# 05_LMS7002M_RF1.net
KiCad netlist of a schematic drawn in Altium Designer
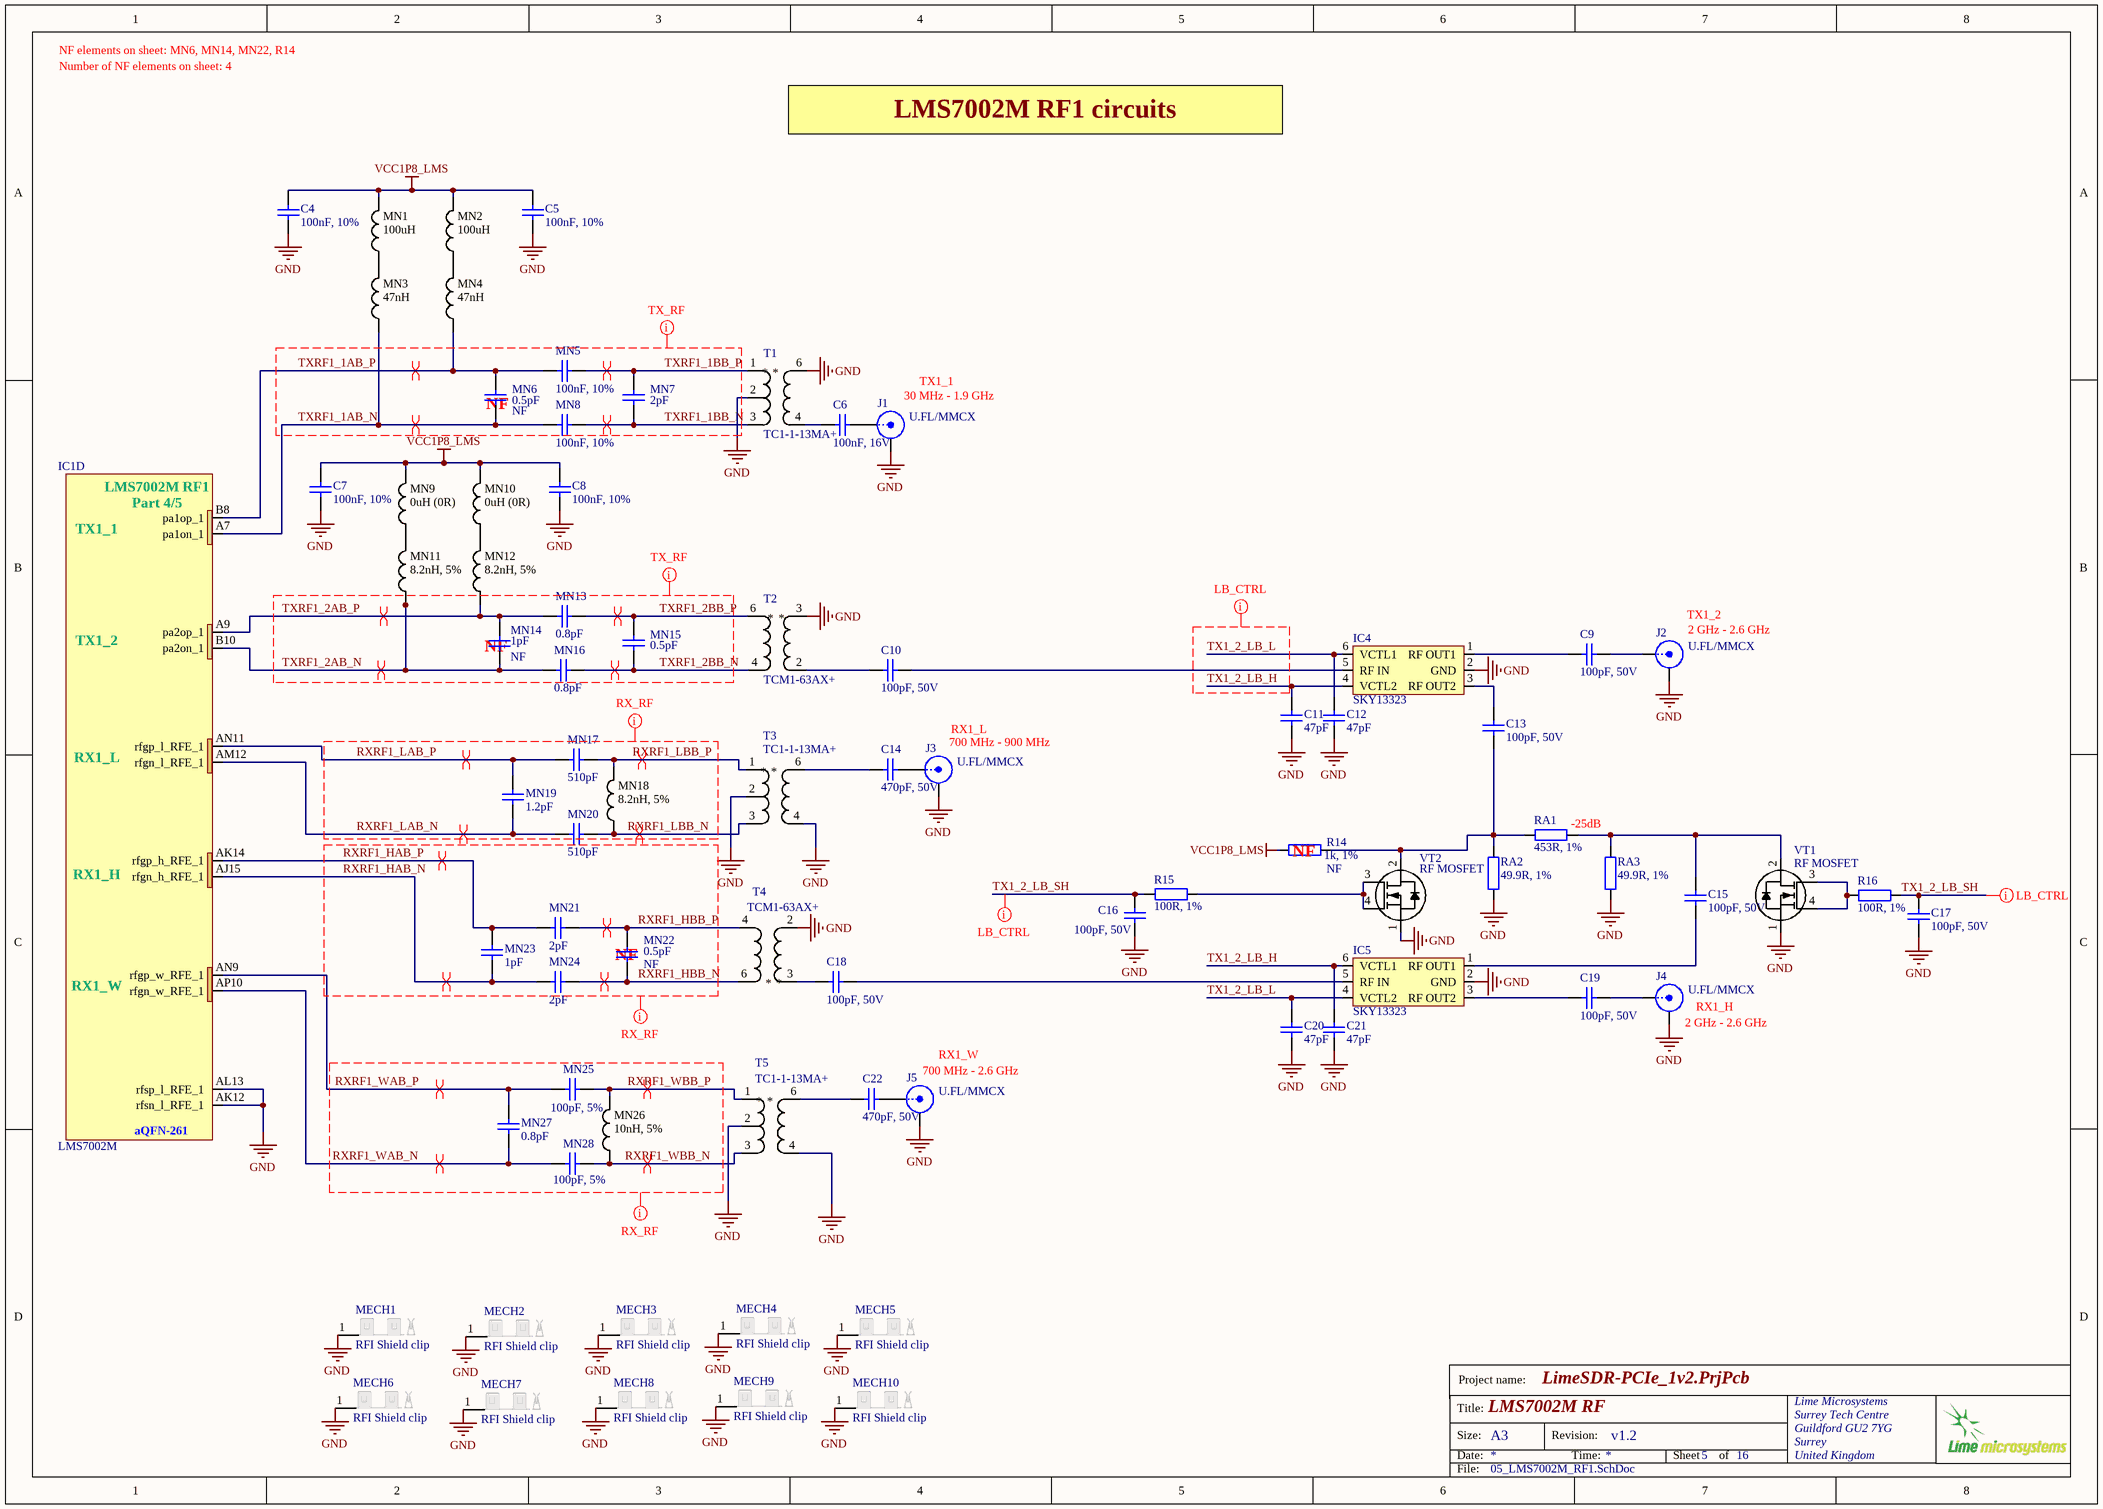
[diagram p0: 05_LMS7002M_RF1.SchDoc]

(export (version "E")
  (design (tool "Eeschema 10.0.6"))
  (components
    (comp (ref "C4")
      (value "100nF, 10%")
      (footprint "CAP0402")
      (fields
        (field (name "MANUFACTURER") "Murata Electronics")
        (field (name "TOLERANCE") "10 %")
        (field (name "MANUFACTURER PART NUMBER") "GRM155R71C104KA88D")
      )
      (libsource (lib "LimeMicroAltiumLib_schLib") (part "Cap_0402"))
    )
    (comp (ref "C5")
      (value "100nF, 10%")
      (footprint "CAP0402")
      (fields
        (field (name "MANUFACTURER") "Murata Electronics")
        (field (name "TOLERANCE") "10 %")
        (field (name "MANUFACTURER PART NUMBER") "GRM155R71C104KA88D")
      )
      (libsource (lib "LimeMicroAltiumLib_schLib") (part "Cap_0402"))
    )
    (comp (ref "C6")
      (value "100nF, 16V")
      (footprint "CAP0402")
      (fields
        (field (name "MANUFACTURER") "Murata Electronics")
        (field (name "TOLERANCE") "10 %")
        (field (name "MANUFACTURER PART NUMBER") "GRM155R71C104KA88D")
      )
      (libsource (lib "LimeMicroAltiumLib_schLib") (part "Cap_0402"))
    )
    (comp (ref "C7")
      (value "100nF, 10%")
      (footprint "CAP0402")
      (fields
        (field (name "MANUFACTURER") "Murata Electronics")
        (field (name "TOLERANCE") "10 %")
        (field (name "MANUFACTURER PART NUMBER") "GRM155R71C104KA88D")
      )
      (libsource (lib "LimeMicroAltiumLib_schLib") (part "Cap_0402"))
    )
    (comp (ref "C8")
      (value "100nF, 10%")
      (footprint "CAP0402")
      (fields
        (field (name "MANUFACTURER") "Murata Electronics")
        (field (name "TOLERANCE") "10 %")
        (field (name "MANUFACTURER PART NUMBER") "GRM155R71C104KA88D")
      )
      (libsource (lib "LimeMicroAltiumLib_schLib") (part "Cap_0402"))
    )
    (comp (ref "C9")
      (value "100pF, 50V")
      (footprint "CAP0402")
      (fields (field (name "TOLERANCE") "±5%") (field (name "MANUFACTURER") "Yageo"))
      (libsource (lib "LimeMicroAltiumLib_schLib") (part "Cap_0402"))
    )
    (comp (ref "C10")
      (value "100pF, 50V")
      (footprint "CAP0402")
      (fields (field (name "TOLERANCE") "±5%") (field (name "MANUFACTURER") "Yageo"))
      (libsource (lib "LimeMicroAltiumLib_schLib") (part "Cap_0402"))
    )
    (comp (ref "C11")
      (value "47pF")
      (footprint "CAP0402")
      (fields (field (name "TOLERANCE") "±1%") (field (name "MANUFACTURER") "TDK Corporation"))
      (libsource (lib "LimeMicroAltiumLib_schLib") (part "Cap_0402"))
    )
    (comp (ref "C12")
      (value "47pF")
      (footprint "CAP0402")
      (fields (field (name "TOLERANCE") "±1%") (field (name "MANUFACTURER") "TDK Corporation"))
      (libsource (lib "LimeMicroAltiumLib_schLib") (part "Cap_0402"))
    )
    (comp (ref "C13")
      (value "100pF, 50V")
      (footprint "CAP0402")
      (fields (field (name "TOLERANCE") "±5%") (field (name "MANUFACTURER") "Yageo"))
      (libsource (lib "LimeMicroAltiumLib_schLib") (part "Cap_0402"))
    )
    (comp (ref "C14")
      (value "470pF, 50V")
      (footprint "CAP0402")
      (fields
        (field (name "MANUFACTURER PART NUMBER") "C1005C0G1H471J050BA")
        (field (name "TOLERANCE") "±5%")
        (field (name "MANUFACTURER") "TDK Corporation")
      )
      (libsource (lib "LimeMicroAltiumLib_schLib") (part "Cap_0402"))
    )
    (comp (ref "C15")
      (value "100pF, 50V")
      (footprint "CAP0402")
      (fields (field (name "TOLERANCE") "±5%") (field (name "MANUFACTURER") "Yageo"))
      (libsource (lib "LimeMicroAltiumLib_schLib") (part "Cap_0402"))
    )
    (comp (ref "C16")
      (value "100pF, 50V")
      (footprint "CAP0402")
      (fields (field (name "TOLERANCE") "±5%") (field (name "MANUFACTURER") "Yageo"))
      (libsource (lib "LimeMicroAltiumLib_schLib") (part "Cap_0402"))
    )
    (comp (ref "C17")
      (value "100pF, 50V")
      (footprint "CAP0402")
      (fields (field (name "TOLERANCE") "±5%") (field (name "MANUFACTURER") "Yageo"))
      (libsource (lib "LimeMicroAltiumLib_schLib") (part "Cap_0402"))
    )
    (comp (ref "C18")
      (value "100pF, 50V")
      (footprint "CAP0402")
      (fields (field (name "TOLERANCE") "±5%") (field (name "MANUFACTURER") "Yageo"))
      (libsource (lib "LimeMicroAltiumLib_schLib") (part "Cap_0402"))
    )
    (comp (ref "C19")
      (value "100pF, 50V")
      (footprint "CAP0402")
      (fields (field (name "TOLERANCE") "±5%") (field (name "MANUFACTURER") "Yageo"))
      (libsource (lib "LimeMicroAltiumLib_schLib") (part "Cap_0402"))
    )
    (comp (ref "C20")
      (value "47pF")
      (footprint "CAP0402")
      (fields (field (name "TOLERANCE") "±1%") (field (name "MANUFACTURER") "TDK Corporation"))
      (libsource (lib "LimeMicroAltiumLib_schLib") (part "Cap_0402"))
    )
    (comp (ref "C21")
      (value "47pF")
      (footprint "CAP0402")
      (fields (field (name "TOLERANCE") "±1%") (field (name "MANUFACTURER") "TDK Corporation"))
      (libsource (lib "LimeMicroAltiumLib_schLib") (part "Cap_0402"))
    )
    (comp (ref "C22")
      (value "470pF, 50V")
      (footprint "CAP0402")
      (fields
        (field (name "MANUFACTURER PART NUMBER") "C1005C0G1H471J050BA")
        (field (name "TOLERANCE") "±5%")
        (field (name "MANUFACTURER") "TDK Corporation")
      )
      (libsource (lib "LimeMicroAltiumLib_schLib") (part "Cap_0402"))
    )
    (comp (ref "IC1")
      (value "LMS7002M")
      (footprint "LMS7002M_v2")
      (fields (field (name "MANUFACTURER") "Lime Microsystems"))
      (libsource (lib "LimeMicroAltiumLib_schLib") (part "LMS7002M"))
    )
    (comp (ref "IC4")
      (value "SKY13323")
      (footprint "SKY13323-378LF")
      (description "SKY13323-378LF: 0.1-3.0 GHz GaAs SPDT Switch")
      (fields (field (name "MANUFACTURER") "Skyworks Solutions Inc."))
      (libsource (lib "LimeMicroAltiumLib_schLib") (part "SKY13323"))
    )
    (comp (ref "IC5")
      (value "SKY13323")
      (footprint "SKY13323-378LF")
      (description "SKY13323-378LF: 0.1-3.0 GHz GaAs SPDT Switch")
      (fields (field (name "MANUFACTURER") "Skyworks Solutions Inc."))
      (libsource (lib "LimeMicroAltiumLib_schLib") (part "SKY13323"))
    )
    (comp (ref "J1")
      (value "U.FL/MMCX")
      (footprint "MMCX_UFL_conn_u")
      (description "CONN UMC RCPT STR 50 OHM SMD")
      (fields (field (name "MANUFACTURER") "Molex, LLC"))
      (libsource (lib "LimeMicroAltiumLib_schLib") (part "RF_IF_connector"))
    )
    (comp (ref "J2")
      (value "U.FL/MMCX")
      (footprint "MMCX_UFL_conn_u")
      (description "CONN UMC RCPT STR 50 OHM SMD")
      (fields (field (name "MANUFACTURER") "Molex, LLC"))
      (libsource (lib "LimeMicroAltiumLib_schLib") (part "RF_IF_connector"))
    )
    (comp (ref "J3")
      (value "U.FL/MMCX")
      (footprint "MMCX_UFL_conn_u")
      (description "CONN UMC RCPT STR 50 OHM SMD")
      (fields (field (name "MANUFACTURER") "Molex, LLC"))
      (libsource (lib "LimeMicroAltiumLib_schLib") (part "RF_IF_connector"))
    )
    (comp (ref "J4")
      (value "U.FL/MMCX")
      (footprint "MMCX_UFL_conn_u")
      (description "CONN UMC RCPT STR 50 OHM SMD")
      (fields (field (name "MANUFACTURER") "Molex, LLC"))
      (libsource (lib "LimeMicroAltiumLib_schLib") (part "RF_IF_connector"))
    )
    (comp (ref "J5")
      (value "U.FL/MMCX")
      (footprint "MMCX_UFL_conn_u")
      (description "CONN UMC RCPT STR 50 OHM SMD")
      (fields (field (name "MANUFACTURER") "Molex, LLC"))
      (libsource (lib "LimeMicroAltiumLib_schLib") (part "RF_IF_connector"))
    )
    (comp (ref "MECH1")
      (value "RFI Shield clip")
      (footprint "RFI_SHIELD_CLPS_MINI")
      (fields (field (name "MANUFACTURER") "HARWIN"))
      (libsource (lib "LimeMicroAltiumLib_schLib") (part "RFI_SHIELD_CLIP"))
    )
    (comp (ref "MECH2")
      (value "RFI Shield clip")
      (footprint "RFI_SHIELD_CLPS_MINI")
      (fields (field (name "MANUFACTURER") "HARWIN"))
      (libsource (lib "LimeMicroAltiumLib_schLib") (part "RFI_SHIELD_CLIP"))
    )
    (comp (ref "MECH3")
      (value "RFI Shield clip")
      (footprint "RFI_SHIELD_CLPS_MINI")
      (fields (field (name "MANUFACTURER") "HARWIN"))
      (libsource (lib "LimeMicroAltiumLib_schLib") (part "RFI_SHIELD_CLIP"))
    )
    (comp (ref "MECH4")
      (value "RFI Shield clip")
      (footprint "RFI_SHIELD_CLPS_MINI")
      (fields (field (name "MANUFACTURER") "HARWIN"))
      (libsource (lib "LimeMicroAltiumLib_schLib") (part "RFI_SHIELD_CLIP"))
    )
    (comp (ref "MECH5")
      (value "RFI Shield clip")
      (footprint "RFI_SHIELD_CLPS_MINI")
      (fields (field (name "MANUFACTURER") "HARWIN"))
      (libsource (lib "LimeMicroAltiumLib_schLib") (part "RFI_SHIELD_CLIP"))
    )
    (comp (ref "MECH6")
      (value "RFI Shield clip")
      (footprint "RFI_SHIELD_CLPS_MINI")
      (fields (field (name "MANUFACTURER") "HARWIN"))
      (libsource (lib "LimeMicroAltiumLib_schLib") (part "RFI_SHIELD_CLIP"))
    )
    (comp (ref "MECH7")
      (value "RFI Shield clip")
      (footprint "RFI_SHIELD_CLPS_MINI")
      (fields (field (name "MANUFACTURER") "HARWIN"))
      (libsource (lib "LimeMicroAltiumLib_schLib") (part "RFI_SHIELD_CLIP"))
    )
    (comp (ref "MECH8")
      (value "RFI Shield clip")
      (footprint "RFI_SHIELD_CLPS_MINI")
      (fields (field (name "MANUFACTURER") "HARWIN"))
      (libsource (lib "LimeMicroAltiumLib_schLib") (part "RFI_SHIELD_CLIP"))
    )
    (comp (ref "MECH9")
      (value "RFI Shield clip")
      (footprint "RFI_SHIELD_CLPS_MINI")
      (fields (field (name "MANUFACTURER") "HARWIN"))
      (libsource (lib "LimeMicroAltiumLib_schLib") (part "RFI_SHIELD_CLIP"))
    )
    (comp (ref "MECH10")
      (value "RFI Shield clip")
      (footprint "RFI_SHIELD_CLPS_MINI")
      (fields (field (name "MANUFACTURER") "HARWIN"))
      (libsource (lib "LimeMicroAltiumLib_schLib") (part "RFI_SHIELD_CLIP"))
    )
    (comp (ref "MN1")
      (value "100uH")
      (footprint "RES0805")
      (fields
        (field (name "TOLERANCE") "±10%")
        (field (name "MANUFACTURER") "TDK Corporation")
        (field (name "MANUFACTURER PART NUMBER") "MLF2012C101KT000")
      )
      (libsource (lib "LimeMicroAltiumLib_schLib") (part "Inductor_0603"))
    )
    (comp (ref "MN2")
      (value "100uH")
      (footprint "RES0805")
      (fields
        (field (name "TOLERANCE") "±10%")
        (field (name "MANUFACTURER") "TDK Corporation")
        (field (name "MANUFACTURER PART NUMBER") "MLF2012C101KT000")
      )
      (libsource (lib "LimeMicroAltiumLib_schLib") (part "Inductor_0603"))
    )
    (comp (ref "MN3")
      (value "47nH")
      (footprint "RES0402")
      (fields
        (field (name "MANUFACTURER") "COILCRAFT")
        (field (name "MANUFACTURER PART NUMBER") "0402HP-47NXJLU")
      )
      (libsource (lib "LimeMicroAltiumLib_schLib") (part "Inductor_0603"))
    )
    (comp (ref "MN4")
      (value "47nH")
      (footprint "RES0402")
      (fields
        (field (name "MANUFACTURER") "COILCRAFT")
        (field (name "MANUFACTURER PART NUMBER") "0402HP-47NXJLU")
      )
      (libsource (lib "LimeMicroAltiumLib_schLib") (part "Inductor_0603"))
    )
    (comp (ref "MN5")
      (value "100nF, 10%")
      (footprint "CAP0402")
      (fields
        (field (name "MANUFACTURER") "Murata Electronics")
        (field (name "TOLERANCE") "10 %")
        (field (name "MANUFACTURER PART NUMBER") "GRM155R71C104KA88D")
      )
      (libsource (lib "LimeMicroAltiumLib_schLib") (part "Cap_0402"))
    )
    (comp (ref "MN6")
      (value "0.5pF")
      (footprint "CAP0402")
      (fields
        (field (name "ASSEMBLY INFO") "NF")
        (field (name "TOLERANCE") "±0.25pF")
        (field (name "MANUFACTURER") "Yageo")
      )
      (libsource (lib "LimeMicroAltiumLib_schLib") (part "Cap_0402"))
    )
    (comp (ref "MN7")
      (value "2pF")
      (footprint "CAP0402")
      (fields (field (name "MANUFACTURER PART NUMBER") "04025U2R0BAT2A") (field (name "MANUFACTURER") "AVX"))
      (libsource (lib "LimeMicroAltiumLib_schLib") (part "Cap_0402"))
    )
    (comp (ref "MN8")
      (value "100nF, 10%")
      (footprint "CAP0402")
      (fields
        (field (name "MANUFACTURER") "Murata Electronics")
        (field (name "TOLERANCE") "10 %")
        (field (name "MANUFACTURER PART NUMBER") "GRM155R71C104KA88D")
      )
      (libsource (lib "LimeMicroAltiumLib_schLib") (part "Cap_0402"))
    )
    (comp (ref "MN9")
      (value "0uH (0R)")
      (footprint "RES0805")
      (fields
        (field (name "MANUFACTURER") "BOURNS")
        (field (name "MANUFACTURER PART NUMBER") "CR0805-J/-000ELF")
      )
      (libsource (lib "LimeMicroAltiumLib_schLib") (part "Inductor_0603"))
    )
    (comp (ref "MN10")
      (value "0uH (0R)")
      (footprint "RES0805")
      (fields
        (field (name "MANUFACTURER") "BOURNS")
        (field (name "MANUFACTURER PART NUMBER") "CR0805-J/-000ELF")
      )
      (libsource (lib "LimeMicroAltiumLib_schLib") (part "Inductor_0603"))
    )
    (comp (ref "MN11")
      (value "8.2nH, 5%")
      (footprint "RES0402")
      (fields (field (name "MANUFACTURER") "COILCRAFT"))
      (libsource (lib "LimeMicroAltiumLib_schLib") (part "Inductor_0603"))
    )
    (comp (ref "MN12")
      (value "8.2nH, 5%")
      (footprint "RES0402")
      (fields (field (name "MANUFACTURER") "COILCRAFT"))
      (libsource (lib "LimeMicroAltiumLib_schLib") (part "Inductor_0603"))
    )
    (comp (ref "MN13")
      (value "0.8pF")
      (footprint "CAP0402")
      (fields
        (field (name "TOLERANCE") "±0.1pF")
        (field (name "MANUFACTURER") "Murata Electronics North America")
        (field (name "MANUFACTURER PART NUMBER") "GRM1555C1HR80BA01D")
      )
      (libsource (lib "LimeMicroAltiumLib_schLib") (part "Cap_0402"))
    )
    (comp (ref "MN14")
      (value "1pF")
      (footprint "CAP0402")
      (fields
        (field (name "ASSEMBLY INFO") "NF")
        (field (name "MANUFACTURER") "TDK Corporation")
        (field (name "TOLERANCE") "±0.1pF")
      )
      (libsource (lib "LimeMicroAltiumLib_schLib") (part "Cap_0402"))
    )
    (comp (ref "MN15")
      (value "0.5pF")
      (footprint "CAP0402")
      (fields (field (name "TOLERANCE") "±0.25pF") (field (name "MANUFACTURER") "Yageo"))
      (libsource (lib "LimeMicroAltiumLib_schLib") (part "Cap_0402"))
    )
    (comp (ref "MN16")
      (value "0.8pF")
      (footprint "CAP0402")
      (fields
        (field (name "TOLERANCE") "±0.1pF")
        (field (name "MANUFACTURER") "Murata Electronics North America")
        (field (name "MANUFACTURER PART NUMBER") "GRM1555C1HR80BA01D")
      )
      (libsource (lib "LimeMicroAltiumLib_schLib") (part "Cap_0402"))
    )
    (comp (ref "MN17")
      (value "510pF")
      (footprint "CAP0402")
      (fields
        (field (name "TOLERANCE") "±5%")
        (field (name "MANUFACTURER") "Murata Electronics North America")
        (field (name "MANUFACTURER PART NUMBER") "GRM1555C1H511JA01D")
      )
      (libsource (lib "LimeMicroAltiumLib_schLib") (part "Cap_0402"))
    )
    (comp (ref "MN18")
      (value "8.2nH, 5%")
      (footprint "RES0402")
      (fields (field (name "MANUFACTURER") "COILCRAFT"))
      (libsource (lib "LimeMicroAltiumLib_schLib") (part "Inductor_0603"))
    )
    (comp (ref "MN19")
      (value "1.2pF")
      (footprint "CAP0402")
      (fields
        (field (name "MANUFACTURER") "Murata Electronics North America")
        (field (name "MANUFACTURER PART NUMBER") "GRM1555C1H1R2CA01D")
        (field (name "TOLERANCE") "±0.25pF")
      )
      (libsource (lib "LimeMicroAltiumLib_schLib") (part "Cap_0402"))
    )
    (comp (ref "MN20")
      (value "510pF")
      (footprint "CAP0402")
      (fields
        (field (name "TOLERANCE") "±5%")
        (field (name "MANUFACTURER") "Murata Electronics North America")
        (field (name "MANUFACTURER PART NUMBER") "GRM1555C1H511JA01D")
      )
      (libsource (lib "LimeMicroAltiumLib_schLib") (part "Cap_0402"))
    )
    (comp (ref "MN21")
      (value "2pF")
      (footprint "CAP0402")
      (fields (field (name "MANUFACTURER PART NUMBER") "04025U2R0BAT2A") (field (name "MANUFACTURER") "AVX"))
      (libsource (lib "LimeMicroAltiumLib_schLib") (part "Cap_0402"))
    )
    (comp (ref "MN22")
      (value "0.5pF")
      (footprint "CAP0402")
      (fields
        (field (name "ASSEMBLY INFO") "NF")
        (field (name "TOLERANCE") "±0.25pF")
        (field (name "MANUFACTURER") "Yageo")
      )
      (libsource (lib "LimeMicroAltiumLib_schLib") (part "Cap_0402"))
    )
    (comp (ref "MN23")
      (value "1pF")
      (footprint "CAP0402")
      (fields (field (name "MANUFACTURER") "TDK Corporation") (field (name "TOLERANCE") "±0.1pF"))
      (libsource (lib "LimeMicroAltiumLib_schLib") (part "Cap_0402"))
    )
    (comp (ref "MN24")
      (value "2pF")
      (footprint "CAP0402")
      (fields (field (name "MANUFACTURER PART NUMBER") "04025U2R0BAT2A") (field (name "MANUFACTURER") "AVX"))
      (libsource (lib "LimeMicroAltiumLib_schLib") (part "Cap_0402"))
    )
    (comp (ref "MN25")
      (value "100pF, 5%")
      (footprint "CAP0402")
      (fields (field (name "TOLERANCE") "±5%") (field (name "MANUFACTURER") "Yageo"))
      (libsource (lib "LimeMicroAltiumLib_schLib") (part "Cap_0402"))
    )
    (comp (ref "MN26")
      (value "10nH, 5%")
      (footprint "RES0402")
      (fields (field (name "MANUFACTURER") "COILCRAFT"))
      (libsource (lib "LimeMicroAltiumLib_schLib") (part "Inductor_0603"))
    )
    (comp (ref "MN27")
      (value "0.8pF")
      (footprint "CAP0402")
      (fields
        (field (name "TOLERANCE") "±0.1pF")
        (field (name "MANUFACTURER") "Murata Electronics North America")
        (field (name "MANUFACTURER PART NUMBER") "GRM1555C1HR80BA01D")
      )
      (libsource (lib "LimeMicroAltiumLib_schLib") (part "Cap_0402"))
    )
    (comp (ref "MN28")
      (value "100pF, 5%")
      (footprint "CAP0402")
      (fields (field (name "TOLERANCE") "±5%") (field (name "MANUFACTURER") "Yageo"))
      (libsource (lib "LimeMicroAltiumLib_schLib") (part "Cap_0402"))
    )
    (comp (ref "R14")
      (value "1k, 1%")
      (footprint "RES0402")
      (fields
        (field (name "ASSEMBLY INFO") "NF")
        (field (name "MANUFACTURER") "Stackpole Electronics Inc")
        (field (name "TOLERANCE") "±1%")
      )
      (libsource (lib "LimeMicroAltiumLib_schLib") (part "Res_0402"))
    )
    (comp (ref "R15")
      (value "100R, 1%")
      (footprint "RES0402")
      (fields (field (name "TOLERANCE") "±1%") (field (name "MANUFACTURER") "Stackpole Electronics Inc."))
      (libsource (lib "LimeFPGAboard_schLib") (part "Res_0402"))
    )
    (comp (ref "R16")
      (value "100R, 1%")
      (footprint "RES0402")
      (fields (field (name "TOLERANCE") "±1%") (field (name "MANUFACTURER") "Stackpole Electronics Inc."))
      (libsource (lib "LimeFPGAboard_schLib") (part "Res_0402"))
    )
    (comp (ref "RA1")
      (value "453R, 1%")
      (footprint "RES0402")
      (fields (field (name "MANUFACTURER") "Yageo") (field (name "TOLERANCE") "±1%"))
      (libsource (lib "LimeMicroAltiumLib_schLib") (part "Res_0402"))
    )
    (comp (ref "RA2")
      (value "49.9R, 1%")
      (footprint "RES0402")
      (fields
        (field (name "TOLERANCE") "±1%")
        (field (name "MANUFACTURER") "Samsung Electro-Mechanics America, Inc.")
        (field (name "MANUFACTURER PART NUMBER") "RC1005F49R9CS")
      )
      (libsource (lib "LimeMicroAltiumLib_schLib") (part "Res_0402"))
    )
    (comp (ref "RA3")
      (value "49.9R, 1%")
      (footprint "RES0402")
      (fields
        (field (name "TOLERANCE") "±1%")
        (field (name "MANUFACTURER") "Samsung Electro-Mechanics America, Inc.")
        (field (name "MANUFACTURER PART NUMBER") "RC1005F49R9CS")
      )
      (libsource (lib "LimeMicroAltiumLib_schLib") (part "Res_0402"))
    )
    (comp (ref "T1")
      (value "TC1-1-13MA+")
      (footprint "TC1-1-13MA+_v2")
      (fields (field (name "MANUFACTURER") "Mini-Circuits"))
      (libsource (lib "LimeMicroAltiumLib_schLib") (part "Balun"))
    )
    (comp (ref "T2")
      (value "TCM1-63AX+")
      (footprint "TCM1-63AX+_v2")
      (fields (field (name "MANUFACTURER") "Mini-circuits"))
      (libsource (lib "LimeMicroAltiumLib_schLib") (part "Balun_v2"))
    )
    (comp (ref "T3")
      (value "TC1-1-13MA+")
      (footprint "TC1-1-13MA+_v2")
      (fields (field (name "MANUFACTURER") "Mini-Circuits"))
      (libsource (lib "LimeMicroAltiumLib_schLib") (part "Balun"))
    )
    (comp (ref "T4")
      (value "TCM1-63AX+")
      (footprint "TCM1-63AX+_v2")
      (fields (field (name "MANUFACTURER") "Mini-circuits"))
      (libsource (lib "") (part "Balun_v2_1"))
    )
    (comp (ref "T5")
      (value "TC1-1-13MA+")
      (footprint "TC1-1-13MA+_v2")
      (fields (field (name "MANUFACTURER") "Mini-Circuits"))
      (libsource (lib "LimeMicroAltiumLib_schLib") (part "Balun"))
    )
    (comp (ref "VT1")
      (value "RF MOSFET")
      (footprint "BF1105R_SOT143R4")
      (fields (field (name "MANUFACTURER") "NXP Semiconductors"))
      (libsource (lib "LimeMicroAltiumLib_schLib") (part "BF1105R,215"))
    )
    (comp (ref "VT2")
      (value "RF MOSFET")
      (footprint "BF1105R_SOT143R4")
      (fields (field (name "MANUFACTURER") "NXP Semiconductors"))
      (libsource (lib "LimeMicroAltiumLib_schLib") (part "BF1105R,215"))
    )
  )
  (nets
    (net (code "1") (name "/RXRF1_HAB_N") (class "Default")
      (node (ref "IC1") (pin "AJ15") (pinfunction "rfgn_h_RFE_1_AJ15") (pintype "passive"))
      (node (ref "MN23") (pin "1") (pinfunction "1_1") (pintype "passive"))
      (node (ref "MN24") (pin "2") (pinfunction "2_2") (pintype "passive"))
    )
    (net (code "2") (name "/RXRF1_HAB_P") (class "Default")
      (node (ref "IC1") (pin "AK14") (pinfunction "rfgp_h_RFE_1_AK14") (pintype "passive"))
      (node (ref "MN21") (pin "2") (pinfunction "2_2") (pintype "passive"))
      (node (ref "MN23") (pin "2") (pinfunction "2_2") (pintype "passive"))
    )
    (net (code "3") (name "/RXRF1_HBB_N") (class "Default")
      (node (ref "MN22") (pin "1") (pinfunction "1_1") (pintype "passive"))
      (node (ref "MN24") (pin "1") (pinfunction "1_1") (pintype "passive"))
      (node (ref "T4") (pin "6") (pinfunction "6_6") (pintype "passive"))
    )
    (net (code "4") (name "/RXRF1_HBB_P") (class "Default")
      (node (ref "MN21") (pin "1") (pinfunction "1_1") (pintype "passive"))
      (node (ref "MN22") (pin "2") (pinfunction "2_2") (pintype "passive"))
      (node (ref "T4") (pin "4") (pinfunction "4_4") (pintype "passive"))
    )
    (net (code "5") (name "/RXRF1_LAB_N") (class "Default")
      (node (ref "IC1") (pin "AM12") (pinfunction "rfgn_l_RFE_1_AM12") (pintype "passive"))
      (node (ref "MN19") (pin "1") (pinfunction "1_1") (pintype "passive"))
      (node (ref "MN20") (pin "2") (pinfunction "2_2") (pintype "passive"))
    )
    (net (code "6") (name "/RXRF1_LAB_P") (class "Default")
      (node (ref "IC1") (pin "AN11") (pinfunction "rfgp_l_RFE_1_AN11") (pintype "passive"))
      (node (ref "MN17") (pin "2") (pinfunction "2_2") (pintype "passive"))
      (node (ref "MN19") (pin "2") (pinfunction "2_2") (pintype "passive"))
    )
    (net (code "7") (name "/RXRF1_LBB_N") (class "Default")
      (node (ref "MN18") (pin "1") (pinfunction "1_1") (pintype "passive"))
      (node (ref "MN20") (pin "1") (pinfunction "1_1") (pintype "passive"))
      (node (ref "T3") (pin "3") (pinfunction "3_3") (pintype "passive"))
    )
    (net (code "8") (name "/RXRF1_LBB_P") (class "Default")
      (node (ref "MN17") (pin "1") (pinfunction "1_1") (pintype "passive"))
      (node (ref "MN18") (pin "2") (pinfunction "2_2") (pintype "passive"))
      (node (ref "T3") (pin "1") (pinfunction "1_1") (pintype "passive"))
    )
    (net (code "9") (name "/RXRF1_WAB_N") (class "Default")
      (node (ref "IC1") (pin "AP10") (pinfunction "rfgn_w_RFE_1_AP10") (pintype "passive"))
      (node (ref "MN27") (pin "2") (pinfunction "2_2") (pintype "passive"))
      (node (ref "MN28") (pin "2") (pinfunction "2_2") (pintype "passive"))
    )
    (net (code "10") (name "/RXRF1_WAB_P") (class "Default")
      (node (ref "IC1") (pin "AN9") (pinfunction "rfgp_w_RFE_1_AN9") (pintype "passive"))
      (node (ref "MN25") (pin "2") (pinfunction "2_2") (pintype "passive"))
      (node (ref "MN27") (pin "1") (pinfunction "1_1") (pintype "passive"))
    )
    (net (code "11") (name "/RXRF1_WBB_N") (class "Default")
      (node (ref "MN26") (pin "1") (pinfunction "1_1") (pintype "passive"))
      (node (ref "MN28") (pin "1") (pinfunction "1_1") (pintype "passive"))
      (node (ref "T5") (pin "3") (pinfunction "3_3") (pintype "passive"))
    )
    (net (code "12") (name "/RXRF1_WBB_P") (class "Default")
      (node (ref "MN25") (pin "1") (pinfunction "1_1") (pintype "passive"))
      (node (ref "MN26") (pin "2") (pinfunction "2_2") (pintype "passive"))
      (node (ref "T5") (pin "1") (pinfunction "1_1") (pintype "passive"))
    )
    (net (code "13") (name "/TX1_2_LB_H") (class "Default")
      (node (ref "C11") (pin "2") (pinfunction "2_2") (pintype "passive"))
      (node (ref "C21") (pin "2") (pinfunction "2_2") (pintype "passive"))
      (node (ref "IC4") (pin "4") (pinfunction "VCTL2_4") (pintype "input"))
      (node (ref "IC5") (pin "6") (pinfunction "VCTL1_6") (pintype "input"))
    )
    (net (code "14") (name "/TX1_2_LB_L") (class "Default")
      (node (ref "C12") (pin "2") (pinfunction "2_2") (pintype "passive"))
      (node (ref "C20") (pin "2") (pinfunction "2_2") (pintype "passive"))
      (node (ref "IC4") (pin "6") (pinfunction "VCTL1_6") (pintype "input"))
      (node (ref "IC5") (pin "4") (pinfunction "VCTL2_4") (pintype "input"))
    )
    (net (code "15") (name "/TX1_2_LB_SH") (class "Default")
      (node (ref "C16") (pin "1") (pinfunction "1_1") (pintype "passive"))
      (node (ref "C17") (pin "1") (pinfunction "1_1") (pintype "passive"))
      (node (ref "R15") (pin "2") (pinfunction "2_2") (pintype "passive"))
      (node (ref "R16") (pin "1") (pinfunction "1_1") (pintype "passive"))
    )
    (net (code "16") (name "/TXRF1_1AB_N") (class "Default")
      (node (ref "IC1") (pin "A7") (pinfunction "pa1on_1_A7") (pintype "passive"))
      (node (ref "MN3") (pin "1") (pinfunction "1_1") (pintype "passive"))
      (node (ref "MN6") (pin "1") (pinfunction "1_1") (pintype "passive"))
      (node (ref "MN8") (pin "1") (pinfunction "1_1") (pintype "passive"))
    )
    (net (code "17") (name "/TXRF1_1AB_P") (class "Default")
      (node (ref "IC1") (pin "B8") (pinfunction "pa1op_1_B8") (pintype "passive"))
      (node (ref "MN4") (pin "1") (pinfunction "1_1") (pintype "passive"))
      (node (ref "MN5") (pin "2") (pinfunction "2_2") (pintype "passive"))
      (node (ref "MN6") (pin "2") (pinfunction "2_2") (pintype "passive"))
    )
    (net (code "18") (name "/TXRF1_1BB_N") (class "Default")
      (node (ref "MN7") (pin "1") (pinfunction "1_1") (pintype "passive"))
      (node (ref "MN8") (pin "2") (pinfunction "2_2") (pintype "passive"))
      (node (ref "T1") (pin "3") (pinfunction "3_3") (pintype "passive"))
    )
    (net (code "19") (name "/TXRF1_1BB_P") (class "Default")
      (node (ref "MN5") (pin "1") (pinfunction "1_1") (pintype "passive"))
      (node (ref "MN7") (pin "2") (pinfunction "2_2") (pintype "passive"))
      (node (ref "T1") (pin "1") (pinfunction "1_1") (pintype "passive"))
    )
    (net (code "20") (name "/TXRF1_2AB_N") (class "Default")
      (node (ref "IC1") (pin "B10") (pinfunction "pa2on_1_B10") (pintype "passive"))
      (node (ref "MN11") (pin "1") (pinfunction "1_1") (pintype "passive"))
      (node (ref "MN14") (pin "2") (pinfunction "2_2") (pintype "passive"))
      (node (ref "MN16") (pin "2") (pinfunction "2_2") (pintype "passive"))
    )
    (net (code "21") (name "/TXRF1_2AB_P") (class "Default")
      (node (ref "IC1") (pin "A9") (pinfunction "pa2op_1_A9") (pintype "passive"))
      (node (ref "MN12") (pin "1") (pinfunction "1_1") (pintype "passive"))
      (node (ref "MN13") (pin "2") (pinfunction "2_2") (pintype "passive"))
      (node (ref "MN14") (pin "1") (pinfunction "1_1") (pintype "passive"))
    )
    (net (code "22") (name "/TXRF1_2BB_N") (class "Default")
      (node (ref "MN15") (pin "1") (pinfunction "1_1") (pintype "passive"))
      (node (ref "MN16") (pin "1") (pinfunction "1_1") (pintype "passive"))
      (node (ref "T2") (pin "4") (pinfunction "4_4") (pintype "passive"))
    )
    (net (code "23") (name "/TXRF1_2BB_P") (class "Default")
      (node (ref "MN13") (pin "1") (pinfunction "1_1") (pintype "passive"))
      (node (ref "MN15") (pin "2") (pinfunction "2_2") (pintype "passive"))
      (node (ref "T2") (pin "6") (pinfunction "6_6") (pintype "passive"))
    )
    (net (code "24") (name "GND") (class "Default")
      (node (ref "C11") (pin "1") (pinfunction "1_1") (pintype "passive"))
      (node (ref "C12") (pin "1") (pinfunction "1_1") (pintype "passive"))
      (node (ref "C16") (pin "2") (pinfunction "2_2") (pintype "passive"))
      (node (ref "C17") (pin "2") (pinfunction "2_2") (pintype "passive"))
      (node (ref "C20") (pin "1") (pinfunction "1_1") (pintype "passive"))
      (node (ref "C21") (pin "1") (pinfunction "1_1") (pintype "passive"))
      (node (ref "C4") (pin "1") (pinfunction "1_1") (pintype "passive"))
      (node (ref "C5") (pin "1") (pinfunction "1_1") (pintype "passive"))
      (node (ref "C7") (pin "1") (pinfunction "1_1") (pintype "passive"))
      (node (ref "C8") (pin "1") (pinfunction "1_1") (pintype "passive"))
      (node (ref "IC1") (pin "AK12") (pinfunction "rfsn_l_RFE_1_AK12") (pintype "passive"))
      (node (ref "IC1") (pin "AL13") (pinfunction "rfsp_l_RFE_1_AL13") (pintype "passive"))
      (node (ref "IC4") (pin "2") (pinfunction "GND_2") (pintype "passive"))
      (node (ref "IC5") (pin "2") (pinfunction "GND_2") (pintype "passive"))
      (node (ref "J1") (pin "2") (pinfunction "Y_2") (pintype "passive"))
      (node (ref "J2") (pin "2") (pinfunction "Y_2") (pintype "passive"))
      (node (ref "J3") (pin "2") (pinfunction "Y_2") (pintype "passive"))
      (node (ref "J4") (pin "2") (pinfunction "Y_2") (pintype "passive"))
      (node (ref "J5") (pin "2") (pinfunction "Y_2") (pintype "passive"))
      (node (ref "MECH1") (pin "1") (pinfunction "GND_1") (pintype "passive"))
      (node (ref "MECH10") (pin "1") (pinfunction "GND_1") (pintype "passive"))
      (node (ref "MECH2") (pin "1") (pinfunction "GND_1") (pintype "passive"))
      (node (ref "MECH3") (pin "1") (pinfunction "GND_1") (pintype "passive"))
      (node (ref "MECH4") (pin "1") (pinfunction "GND_1") (pintype "passive"))
      (node (ref "MECH5") (pin "1") (pinfunction "GND_1") (pintype "passive"))
      (node (ref "MECH6") (pin "1") (pinfunction "GND_1") (pintype "passive"))
      (node (ref "MECH7") (pin "1") (pinfunction "GND_1") (pintype "passive"))
      (node (ref "MECH8") (pin "1") (pinfunction "GND_1") (pintype "passive"))
      (node (ref "MECH9") (pin "1") (pinfunction "GND_1") (pintype "passive"))
      (node (ref "RA2") (pin "1") (pinfunction "1_1") (pintype "passive"))
      (node (ref "RA3") (pin "1") (pinfunction "1_1") (pintype "passive"))
      (node (ref "T1") (pin "2") (pinfunction "2_2") (pintype "passive"))
      (node (ref "T1") (pin "6") (pinfunction "6_6") (pintype "passive"))
      (node (ref "T2") (pin "3") (pinfunction "3_3") (pintype "passive"))
      (node (ref "T3") (pin "2") (pinfunction "2_2") (pintype "passive"))
      (node (ref "T3") (pin "4") (pinfunction "4_4") (pintype "passive"))
      (node (ref "T4") (pin "2") (pinfunction "2_2") (pintype "passive"))
      (node (ref "T5") (pin "2") (pinfunction "2_2") (pintype "passive"))
      (node (ref "T5") (pin "4") (pinfunction "4_4") (pintype "passive"))
      (node (ref "VT1") (pin "1") (pinfunction "S_1") (pintype "passive"))
      (node (ref "VT2") (pin "1") (pinfunction "S_1") (pintype "passive"))
    )
    (net (code "25") (name "Net-(C6-Pad2)") (class "Default")
      (node (ref "C6") (pin "2") (pinfunction "2_2") (pintype "passive"))
      (node (ref "T1") (pin "4") (pinfunction "4_4") (pintype "passive"))
    )
    (net (code "26") (name "Net-(C10-Pad2)") (class "Default")
      (node (ref "C10") (pin "2") (pinfunction "2_2") (pintype "passive"))
      (node (ref "T2") (pin "2") (pinfunction "2_2") (pintype "passive"))
    )
    (net (code "27") (name "Net-(C14-Pad2)") (class "Default")
      (node (ref "C14") (pin "2") (pinfunction "2_2") (pintype "passive"))
      (node (ref "T3") (pin "6") (pinfunction "6_6") (pintype "passive"))
    )
    (net (code "28") (name "Net-(C18-Pad2)") (class "Default")
      (node (ref "C18") (pin "2") (pinfunction "2_2") (pintype "passive"))
      (node (ref "T4") (pin "3") (pinfunction "3_3") (pintype "passive"))
    )
    (net (code "29") (name "Net-(C22-Pad2)") (class "Default")
      (node (ref "C22") (pin "2") (pinfunction "2_2") (pintype "passive"))
      (node (ref "T5") (pin "6") (pinfunction "6_6") (pintype "passive"))
    )
    (net (code "30") (name "Net-(IC4-RF_IN)") (class "Default")
      (node (ref "C10") (pin "1") (pinfunction "1_1") (pintype "passive"))
      (node (ref "IC4") (pin "5") (pinfunction "RF_IN_5") (pintype "input"))
    )
    (net (code "31") (name "Net-(IC4-RF_OUT1)") (class "Default")
      (node (ref "C9") (pin "2") (pinfunction "2_2") (pintype "passive"))
      (node (ref "IC4") (pin "1") (pinfunction "RF_OUT1_1") (pintype "output"))
    )
    (net (code "32") (name "Net-(IC4-RF_OUT2)") (class "Default")
      (node (ref "C13") (pin "1") (pinfunction "1_1") (pintype "passive"))
      (node (ref "IC4") (pin "3") (pinfunction "RF_OUT2_3") (pintype "output"))
    )
    (net (code "33") (name "Net-(IC5-RF_IN)") (class "Default")
      (node (ref "C18") (pin "1") (pinfunction "1_1") (pintype "passive"))
      (node (ref "IC5") (pin "5") (pinfunction "RF_IN_5") (pintype "input"))
    )
    (net (code "34") (name "Net-(IC5-RF_OUT1)") (class "Default")
      (node (ref "C15") (pin "2") (pinfunction "2_2") (pintype "passive"))
      (node (ref "IC5") (pin "1") (pinfunction "RF_OUT1_1") (pintype "output"))
    )
    (net (code "35") (name "Net-(IC5-RF_OUT2)") (class "Default")
      (node (ref "C19") (pin "2") (pinfunction "2_2") (pintype "passive"))
      (node (ref "IC5") (pin "3") (pinfunction "RF_OUT2_3") (pintype "output"))
    )
    (net (code "36") (name "Net-(J1-X)") (class "Default")
      (node (ref "C6") (pin "1") (pinfunction "1_1") (pintype "passive"))
      (node (ref "J1") (pin "1") (pinfunction "X_1") (pintype "passive"))
    )
    (net (code "37") (name "Net-(J2-X)") (class "Default")
      (node (ref "C9") (pin "1") (pinfunction "1_1") (pintype "passive"))
      (node (ref "J2") (pin "1") (pinfunction "X_1") (pintype "passive"))
    )
    (net (code "38") (name "Net-(J3-X)") (class "Default")
      (node (ref "C14") (pin "1") (pinfunction "1_1") (pintype "passive"))
      (node (ref "J3") (pin "1") (pinfunction "X_1") (pintype "passive"))
    )
    (net (code "39") (name "Net-(J4-X)") (class "Default")
      (node (ref "C19") (pin "1") (pinfunction "1_1") (pintype "passive"))
      (node (ref "J4") (pin "1") (pinfunction "X_1") (pintype "passive"))
    )
    (net (code "40") (name "Net-(J5-X)") (class "Default")
      (node (ref "C22") (pin "1") (pinfunction "1_1") (pintype "passive"))
      (node (ref "J5") (pin "1") (pinfunction "X_1") (pintype "passive"))
    )
    (net (code "41") (name "Net-(MN1-Pad1)") (class "Default")
      (node (ref "MN1") (pin "1") (pinfunction "1_1") (pintype "passive"))
      (node (ref "MN3") (pin "2") (pinfunction "2_2") (pintype "passive"))
    )
    (net (code "42") (name "Net-(MN2-Pad1)") (class "Default")
      (node (ref "MN2") (pin "1") (pinfunction "1_1") (pintype "passive"))
      (node (ref "MN4") (pin "2") (pinfunction "2_2") (pintype "passive"))
    )
    (net (code "43") (name "Net-(MN10-Pad1)") (class "Default")
      (node (ref "MN10") (pin "1") (pinfunction "1_1") (pintype "passive"))
      (node (ref "MN12") (pin "2") (pinfunction "2_2") (pintype "passive"))
    )
    (net (code "44") (name "Net-(MN11-Pad2)") (class "Default")
      (node (ref "MN11") (pin "2") (pinfunction "2_2") (pintype "passive"))
      (node (ref "MN9") (pin "1") (pinfunction "1_1") (pintype "passive"))
    )
    (net (code "45") (name "Net-(VT1-D)") (class "Default")
      (node (ref "C15") (pin "1") (pinfunction "1_1") (pintype "passive"))
      (node (ref "RA1") (pin "2") (pinfunction "2_2") (pintype "passive"))
      (node (ref "RA3") (pin "2") (pinfunction "2_2") (pintype "passive"))
      (node (ref "VT1") (pin "2") (pinfunction "D_2") (pintype "passive"))
    )
    (net (code "46") (name "Net-(VT1-G1)") (class "Default")
      (node (ref "R16") (pin "2") (pinfunction "2_2") (pintype "passive"))
      (node (ref "VT1") (pin "3") (pinfunction "G2_3") (pintype "passive"))
      (node (ref "VT1") (pin "4") (pinfunction "G1_4") (pintype "passive"))
    )
    (net (code "47") (name "Net-(VT2-D)") (class "Default")
      (node (ref "C13") (pin "2") (pinfunction "2_2") (pintype "passive"))
      (node (ref "R14") (pin "1") (pinfunction "1_1") (pintype "passive"))
      (node (ref "RA1") (pin "1") (pinfunction "1_1") (pintype "passive"))
      (node (ref "RA2") (pin "2") (pinfunction "2_2") (pintype "passive"))
      (node (ref "VT2") (pin "2") (pinfunction "D_2") (pintype "passive"))
    )
    (net (code "48") (name "Net-(VT2-G1)") (class "Default")
      (node (ref "R15") (pin "1") (pinfunction "1_1") (pintype "passive"))
      (node (ref "VT2") (pin "3") (pinfunction "G2_3") (pintype "passive"))
      (node (ref "VT2") (pin "4") (pinfunction "G1_4") (pintype "passive"))
    )
    (net (code "49") (name "VCC1P8_LMS") (class "Default")
      (node (ref "C4") (pin "2") (pinfunction "2_2") (pintype "passive"))
      (node (ref "C5") (pin "2") (pinfunction "2_2") (pintype "passive"))
      (node (ref "C7") (pin "2") (pinfunction "2_2") (pintype "passive"))
      (node (ref "C8") (pin "2") (pinfunction "2_2") (pintype "passive"))
      (node (ref "MN1") (pin "2") (pinfunction "2_2") (pintype "passive"))
      (node (ref "MN10") (pin "2") (pinfunction "2_2") (pintype "passive"))
      (node (ref "MN2") (pin "2") (pinfunction "2_2") (pintype "passive"))
      (node (ref "MN9") (pin "2") (pinfunction "2_2") (pintype "passive"))
      (node (ref "R14") (pin "2") (pinfunction "2_2") (pintype "passive"))
    )
  )
)
